# STM32MP25XXAK_I_Os.net
KiCad netlist of a schematic drawn in Altium Designer
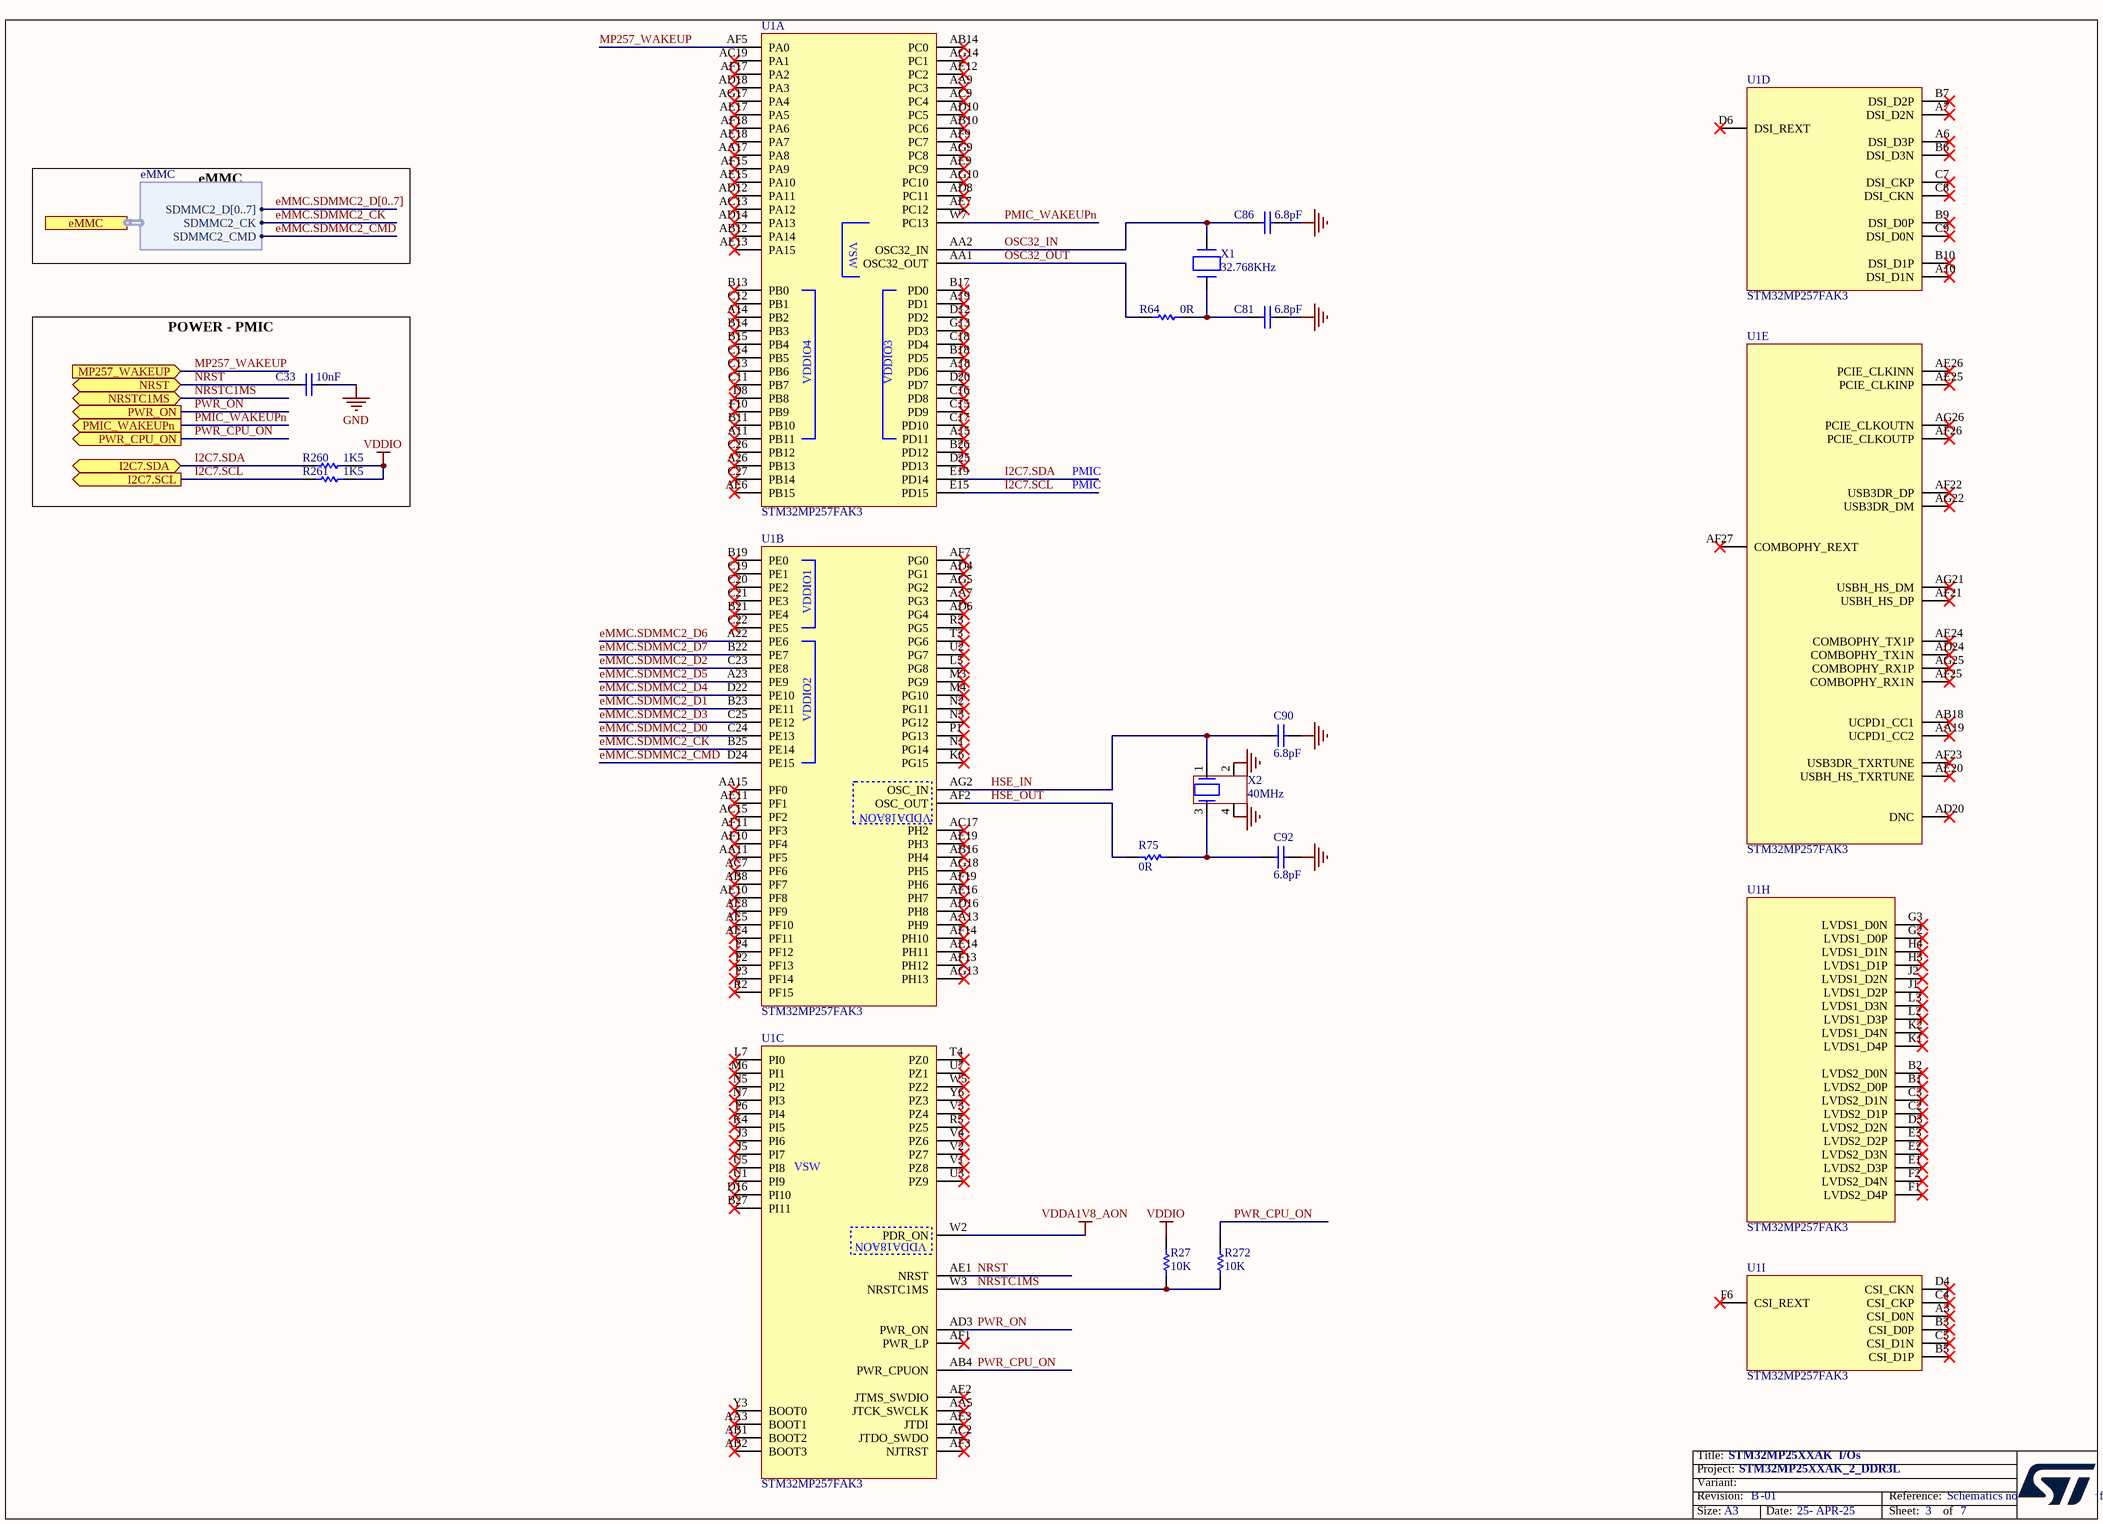
[diagram p0: STM32MP25XXAK I_Os.SchDoc]

(export (version "E")
  (design (tool "Eeschema 10.0.6"))
  (components
    (comp (ref "C33")
      (value "10nF")
      (footprint "C0402")
      (description "Capacitor, MLCC, 10nF, 16V, X7R, 10%, 0402, T=0.5mm")
      (fields
        (field (name "INTERNAL_PART_NUMBER") "MCD-00011")
        (field (name "MANUFACTURER_PART_NUMBER") "CC0402KRX7R7BB103")
        (field (name "PROVIDED_BY") "SUBCO")
      )
      (libsource (lib "MCD_PARTS_database") (part "Capacitor"))
    )
    (comp (ref "C81")
      (value "6.8pF")
      (footprint "C0402")
      (description "Capacitor, MLCC, 6.8pF, 50V, NPO, +-0.25pF, 0402, T=0.5mm")
      (fields
        (field (name "INTERNAL_PART_NUMBER") "MCD-00674")
        (field (name "MANUFACTURER_PART_NUMBER") "CC0402CRNPO9BN6R8")
        (field (name "PROVIDED_BY") "SUBCO")
      )
      (libsource (lib "MCD_PARTS_database") (part "Capacitor"))
    )
    (comp (ref "C86")
      (value "6.8pF")
      (footprint "C0402")
      (description "Capacitor, MLCC, 6.8pF, 50V, NPO, +-0.25pF, 0402, T=0.5mm")
      (fields
        (field (name "INTERNAL_PART_NUMBER") "MCD-00674")
        (field (name "MANUFACTURER_PART_NUMBER") "CC0402CRNPO9BN6R8")
        (field (name "PROVIDED_BY") "SUBCO")
      )
      (libsource (lib "MCD_PARTS_database") (part "Capacitor"))
    )
    (comp (ref "C90")
      (value "6.8pF")
      (footprint "C0402")
      (description "Capacitor, MLCC, 6.8pF, 50V, NPO, +-0.25pF, 0402, T=0.5mm")
      (fields
        (field (name "INTERNAL_PART_NUMBER") "MCD-00674")
        (field (name "MANUFACTURER_PART_NUMBER") "CC0402CRNPO9BN6R8")
        (field (name "PROVIDED_BY") "SUBCO")
      )
      (libsource (lib "MCD_PARTS_database") (part "Capacitor"))
    )
    (comp (ref "C92")
      (value "6.8pF")
      (footprint "C0402")
      (description "Capacitor, MLCC, 6.8pF, 50V, NPO, +-0.25pF, 0402, T=0.5mm")
      (fields
        (field (name "INTERNAL_PART_NUMBER") "MCD-00674")
        (field (name "MANUFACTURER_PART_NUMBER") "CC0402CRNPO9BN6R8")
        (field (name "PROVIDED_BY") "SUBCO")
      )
      (libsource (lib "MCD_PARTS_database") (part "Capacitor"))
    )
    (comp (ref "R27")
      (value "10K")
      (footprint "R0402")
      (description "Resistor,10K,0402,1%,1/16W")
      (fields (field (name "INTERNAL_PART_NUMBER") "MCD-00053") (field (name "BMS_PART_NUMBER") "9131590"))
      (libsource (lib "MCD_PARTS_database") (part "Resistor"))
    )
    (comp (ref "R64")
      (value "0R")
      (footprint "R0402")
      (description "Resistor,0R,0402,5%,1/16W")
      (fields
        (field (name "INTERNAL_PART_NUMBER") "MCD-00052")
        (field (name "MANUFACTURER_PART_NUMBER") "RC0402JR-070RL")
        (field (name "PROVIDED_BY") "SUBCO")
      )
      (libsource (lib "MCD_PARTS_database") (part "Resistor"))
    )
    (comp (ref "R75")
      (value "0R")
      (footprint "R0402")
      (description "Resistor,0R,0402,5%,1/16W")
      (fields
        (field (name "INTERNAL_PART_NUMBER") "MCD-00052")
        (field (name "MANUFACTURER_PART_NUMBER") "RC0402JR-070RL")
        (field (name "PROVIDED_BY") "SUBCO")
      )
      (libsource (lib "MCD_PARTS_database") (part "Resistor"))
    )
    (comp (ref "R260")
      (value "1K5")
      (footprint "R0402")
      (description "Resistor,1K5,0402,1%,1/16W")
      (fields (field (name "INTERNAL_PART_NUMBER") "MCD-00068") (field (name "MANUFACTURER") "YAGEO"))
      (libsource (lib "MCD_PARTS_database") (part "Resistor"))
    )
    (comp (ref "R261")
      (value "1K5")
      (footprint "R0402")
      (description "Resistor,1K5,0402,1%,1/16W")
      (fields (field (name "INTERNAL_PART_NUMBER") "MCD-00068") (field (name "MANUFACTURER") "YAGEO"))
      (libsource (lib "MCD_PARTS_database") (part "Resistor"))
    )
    (comp (ref "R272")
      (value "10K")
      (footprint "R0402")
      (description "Resistor,10K,0402,1%,1/16W")
      (fields (field (name "INTERNAL_PART_NUMBER") "MCD-00053") (field (name "BMS_PART_NUMBER") "9131590"))
      (libsource (lib "MCD_PARTS_database") (part "Resistor"))
    )
    (comp (ref "U1")
      (value "STM32MP257FAK3")
      (footprint "ICC_TFBGA424_14X14_P050_H1P20_CODE-B0A2")
      (description "MPU , 2xCortex-A35@1.5GHz, Cortex-M33@400MHz, TFBGA 14x14, pitch 0.5, 648KB SRAM, With Crypto")
      (fields
        (field (name "INTERNAL_PART_NUMBER") "MCD-03375")
        (field (name "MANUFACTURER") "STMICROELECTRONICS")
      )
      (libsource (lib "MCD_PARTS_database") (part "STM32MP257FAK3"))
    )
    (comp (ref "X1")
      (value "32.768KHz")
      (footprint "CRY_NX2012SA_2P")
      (description "Crystal, 32.768kHz, 6pF, +/-20ppm, 80K, 2.05x1.2mm")
      (fields (field (name "INTERNAL_PART_NUMBER") "MCD-01479") (field (name "BMS_PART_NUMBER") "9157049"))
      (libsource (lib "MCD_PARTS_database") (part "XTAL_2_PINS"))
    )
    (comp (ref "X2")
      (value "40MHz")
      (footprint "CRY_NX1612SA_4P")
      (description "Crystal, 40MHz, 6pF, +/-20ppm, 80R, 1.6x1.2mm")
      (fields (field (name "INTERNAL_PART_NUMBER") "MCD-02344") (field (name "MANUFACTURER") "NDK"))
      (libsource (lib "MCD_PARTS_database") (part "XTAL_4_PINS"))
    )
  )
  (nets
    (net (code "2") (name "/HSE_IN") (class "Default")
      (node (ref "C90") (pin "2") (pinfunction "2_2") (pintype "passive"))
      (node (ref "U1") (pin "AG2") (pinfunction "OSC_IN_AG2") (pintype "passive"))
      (node (ref "X2") (pin "1") (pinfunction "1_1") (pintype "passive"))
    )
    (net (code "3") (name "/HSE_OUT") (class "Default")
      (node (ref "R75") (pin "2") (pinfunction "2_2") (pintype "passive"))
      (node (ref "U1") (pin "AF2") (pinfunction "OSC_OUT_AF2") (pintype "passive"))
    )
    (net (code "4") (name "/I2C7.SCL") (class "Default")
      (node (ref "R261") (pin "1") (pinfunction "1_1") (pintype "passive"))
      (node (ref "U1") (pin "E15") (pinfunction "PD15_E15") (pintype "passive"))
    )
    (net (code "5") (name "/I2C7.SDA") (class "Default")
      (node (ref "R260") (pin "1") (pinfunction "1_1") (pintype "passive"))
      (node (ref "U1") (pin "E19") (pinfunction "PD14_E19") (pintype "passive"))
    )
    (net (code "6") (name "/MP257_WAKEUP") (class "Default")
      (node (ref "U1") (pin "AF5") (pinfunction "PA0_AF5") (pintype "passive"))
    )
    (net (code "7") (name "/NRST") (class "Default")
      (node (ref "C33") (pin "2") (pinfunction "2_2") (pintype "passive"))
      (node (ref "U1") (pin "AE1") (pinfunction "NRST_AE1") (pintype "passive"))
    )
    (net (code "8") (name "/NRSTC1MS") (class "Default")
      (node (ref "R27") (pin "1") (pinfunction "1_1") (pintype "passive"))
      (node (ref "R272") (pin "1") (pinfunction "1_1") (pintype "passive"))
      (node (ref "U1") (pin "W3") (pinfunction "NRSTC1MS_W3") (pintype "passive"))
    )
    (net (code "9") (name "/OSC32_IN") (class "Default")
      (node (ref "C86") (pin "1") (pinfunction "1_1") (pintype "passive"))
      (node (ref "U1") (pin "AA2") (pinfunction "OSC32_IN_AA2") (pintype "passive"))
      (node (ref "X1") (pin "2") (pinfunction "X2_2") (pintype "passive"))
    )
    (net (code "10") (name "/OSC32_OUT") (class "Default")
      (node (ref "R64") (pin "1") (pinfunction "1_1") (pintype "passive"))
      (node (ref "U1") (pin "AA1") (pinfunction "OSC32_OUT_AA1") (pintype "passive"))
    )
    (net (code "11") (name "/PMIC_WAKEUPn") (class "Default")
      (node (ref "U1") (pin "W7") (pinfunction "PC13_W7") (pintype "passive"))
    )
    (net (code "12") (name "/PWR_CPU_ON") (class "Default")
      (node (ref "R272") (pin "2") (pinfunction "2_2") (pintype "passive"))
      (node (ref "U1") (pin "AB4") (pinfunction "PWR_CPUON_AB4") (pintype "passive"))
    )
    (net (code "13") (name "/PWR_ON") (class "Default")
      (node (ref "U1") (pin "AD3") (pinfunction "PWR_ON_AD3") (pintype "passive"))
    )
    (net (code "14") (name "/eMMC.SDMMC2_CK") (class "Default")
      (node (ref "U1") (pin "B25") (pinfunction "PE14_B25") (pintype "passive"))
    )
    (net (code "15") (name "/eMMC.SDMMC2_CMD") (class "Default")
      (node (ref "U1") (pin "D24") (pinfunction "PE15_D24") (pintype "passive"))
    )
    (net (code "16") (name "/eMMC.SDMMC2_D0") (class "Default")
      (node (ref "U1") (pin "C24") (pinfunction "PE13_C24") (pintype "passive"))
    )
    (net (code "17") (name "/eMMC.SDMMC2_D1") (class "Default")
      (node (ref "U1") (pin "B23") (pinfunction "PE11_B23") (pintype "passive"))
    )
    (net (code "18") (name "/eMMC.SDMMC2_D2") (class "Default")
      (node (ref "U1") (pin "C23") (pinfunction "PE8_C23") (pintype "passive"))
    )
    (net (code "19") (name "/eMMC.SDMMC2_D3") (class "Default")
      (node (ref "U1") (pin "C25") (pinfunction "PE12_C25") (pintype "passive"))
    )
    (net (code "20") (name "/eMMC.SDMMC2_D4") (class "Default")
      (node (ref "U1") (pin "D22") (pinfunction "PE10_D22") (pintype "passive"))
    )
    (net (code "21") (name "/eMMC.SDMMC2_D5") (class "Default")
      (node (ref "U1") (pin "A23") (pinfunction "PE9_A23") (pintype "passive"))
    )
    (net (code "22") (name "/eMMC.SDMMC2_D6") (class "Default")
      (node (ref "U1") (pin "A22") (pinfunction "PE6_A22") (pintype "passive"))
    )
    (net (code "23") (name "/eMMC.SDMMC2_D7") (class "Default")
      (node (ref "U1") (pin "B22") (pinfunction "PE7_B22") (pintype "passive"))
    )
    (net (code "26") (name "GND") (class "Default")
      (node (ref "C33") (pin "1") (pinfunction "1_1") (pintype "passive"))
      (node (ref "C81") (pin "2") (pinfunction "2_2") (pintype "passive"))
      (node (ref "C86") (pin "2") (pinfunction "2_2") (pintype "passive"))
      (node (ref "C90") (pin "1") (pinfunction "1_1") (pintype "passive"))
      (node (ref "C92") (pin "2") (pinfunction "2_2") (pintype "passive"))
      (node (ref "X2") (pin "2") (pinfunction "2_2") (pintype "passive"))
      (node (ref "X2") (pin "4") (pinfunction "4_4") (pintype "passive"))
    )
    (net (code "27") (name "Net-(C92-Pad1)") (class "Default")
      (node (ref "C92") (pin "1") (pinfunction "1_1") (pintype "passive"))
      (node (ref "R75") (pin "1") (pinfunction "1_1") (pintype "passive"))
      (node (ref "X2") (pin "3") (pinfunction "3_3") (pintype "passive"))
    )
    (net (code "28") (name "Net-(X1-X1)") (class "Default")
      (node (ref "C81") (pin "1") (pinfunction "1_1") (pintype "passive"))
      (node (ref "R64") (pin "2") (pinfunction "2_2") (pintype "passive"))
      (node (ref "X1") (pin "1") (pinfunction "X1_1") (pintype "passive"))
    )
    (net (code "29") (name "VDDA1V8_AON") (class "Default")
      (node (ref "U1") (pin "W2") (pinfunction "PDR_ON_W2") (pintype "passive"))
    )
    (net (code "30") (name "VDDIO") (class "Default")
      (node (ref "R260") (pin "2") (pinfunction "2_2") (pintype "passive"))
      (node (ref "R261") (pin "2") (pinfunction "2_2") (pintype "passive"))
      (node (ref "R27") (pin "2") (pinfunction "2_2") (pintype "passive"))
    )
    (net (code "31") (name "unconnected-(U1A-PA1-PadAC19)") (class "Default")
      (node (ref "U1") (pin "AC19") (pinfunction "PA1_AC19") (pintype "passive+no_connect"))
    )
    (net (code "32") (name "unconnected-(U1A-PA2-PadAF17)") (class "Default")
      (node (ref "U1") (pin "AF17") (pinfunction "PA2_AF17") (pintype "passive+no_connect"))
    )
    (net (code "33") (name "unconnected-(U1A-PA3-PadAD18)") (class "Default")
      (node (ref "U1") (pin "AD18") (pinfunction "PA3_AD18") (pintype "passive+no_connect"))
    )
    (net (code "34") (name "unconnected-(U1A-PA4-PadAG17)") (class "Default")
      (node (ref "U1") (pin "AG17") (pinfunction "PA4_AG17") (pintype "passive+no_connect"))
    )
    (net (code "35") (name "unconnected-(U1A-PA5-PadAE17)") (class "Default")
      (node (ref "U1") (pin "AE17") (pinfunction "PA5_AE17") (pintype "passive+no_connect"))
    )
    (net (code "36") (name "unconnected-(U1A-PA6-PadAF18)") (class "Default")
      (node (ref "U1") (pin "AF18") (pinfunction "PA6_AF18") (pintype "passive+no_connect"))
    )
    (net (code "37") (name "unconnected-(U1A-PA7-PadAE18)") (class "Default")
      (node (ref "U1") (pin "AE18") (pinfunction "PA7_AE18") (pintype "passive+no_connect"))
    )
    (net (code "38") (name "unconnected-(U1A-PA8-PadAA17)") (class "Default")
      (node (ref "U1") (pin "AA17") (pinfunction "PA8_AA17") (pintype "passive+no_connect"))
    )
    (net (code "39") (name "unconnected-(U1A-PA9-PadAF15)") (class "Default")
      (node (ref "U1") (pin "AF15") (pinfunction "PA9_AF15") (pintype "passive+no_connect"))
    )
    (net (code "40") (name "unconnected-(U1A-PA10-PadAE15)") (class "Default")
      (node (ref "U1") (pin "AE15") (pinfunction "PA10_AE15") (pintype "passive+no_connect"))
    )
    (net (code "41") (name "unconnected-(U1A-PA11-PadAD12)") (class "Default")
      (node (ref "U1") (pin "AD12") (pinfunction "PA11_AD12") (pintype "passive+no_connect"))
    )
    (net (code "42") (name "unconnected-(U1A-PA12-PadAC13)") (class "Default")
      (node (ref "U1") (pin "AC13") (pinfunction "PA12_AC13") (pintype "passive+no_connect"))
    )
    (net (code "43") (name "unconnected-(U1A-PA13-PadAD14)") (class "Default")
      (node (ref "U1") (pin "AD14") (pinfunction "PA13_AD14") (pintype "passive+no_connect"))
    )
    (net (code "44") (name "unconnected-(U1A-PA14-PadAB12)") (class "Default")
      (node (ref "U1") (pin "AB12") (pinfunction "PA14_AB12") (pintype "passive+no_connect"))
    )
    (net (code "45") (name "unconnected-(U1A-PA15-PadAE13)") (class "Default")
      (node (ref "U1") (pin "AE13") (pinfunction "PA15_AE13") (pintype "passive+no_connect"))
    )
    (net (code "46") (name "unconnected-(U1A-PB0-PadB13)") (class "Default")
      (node (ref "U1") (pin "B13") (pinfunction "PB0_B13") (pintype "passive+no_connect"))
    )
    (net (code "47") (name "unconnected-(U1A-PB1-PadC12)") (class "Default")
      (node (ref "U1") (pin "C12") (pinfunction "PB1_C12") (pintype "passive+no_connect"))
    )
    (net (code "48") (name "unconnected-(U1A-PB2-PadA14)") (class "Default")
      (node (ref "U1") (pin "A14") (pinfunction "PB2_A14") (pintype "passive+no_connect"))
    )
    (net (code "49") (name "unconnected-(U1A-PB3-PadB14)") (class "Default")
      (node (ref "U1") (pin "B14") (pinfunction "PB3_B14") (pintype "passive+no_connect"))
    )
    (net (code "50") (name "unconnected-(U1A-PB4-PadB15)") (class "Default")
      (node (ref "U1") (pin "B15") (pinfunction "PB4_B15") (pintype "passive+no_connect"))
    )
    (net (code "51") (name "unconnected-(U1A-PB5-PadC14)") (class "Default")
      (node (ref "U1") (pin "C14") (pinfunction "PB5_C14") (pintype "passive+no_connect"))
    )
    (net (code "52") (name "unconnected-(U1A-PB6-PadC13)") (class "Default")
      (node (ref "U1") (pin "C13") (pinfunction "PB6_C13") (pintype "passive+no_connect"))
    )
    (net (code "53") (name "unconnected-(U1A-PB7-PadC11)") (class "Default")
      (node (ref "U1") (pin "C11") (pinfunction "PB7_C11") (pintype "passive+no_connect"))
    )
    (net (code "54") (name "unconnected-(U1A-PB8-PadD8)") (class "Default")
      (node (ref "U1") (pin "D8") (pinfunction "PB8_D8") (pintype "passive+no_connect"))
    )
    (net (code "55") (name "unconnected-(U1A-PB9-PadF10)") (class "Default")
      (node (ref "U1") (pin "F10") (pinfunction "PB9_F10") (pintype "passive+no_connect"))
    )
    (net (code "56") (name "unconnected-(U1A-PB10-PadB11)") (class "Default")
      (node (ref "U1") (pin "B11") (pinfunction "PB10_B11") (pintype "passive+no_connect"))
    )
    (net (code "57") (name "unconnected-(U1A-PB11-PadA11)") (class "Default")
      (node (ref "U1") (pin "A11") (pinfunction "PB11_A11") (pintype "passive+no_connect"))
    )
    (net (code "58") (name "unconnected-(U1A-PB12-PadC26)") (class "Default")
      (node (ref "U1") (pin "C26") (pinfunction "PB12_C26") (pintype "passive+no_connect"))
    )
    (net (code "59") (name "unconnected-(U1A-PB13-PadA26)") (class "Default")
      (node (ref "U1") (pin "A26") (pinfunction "PB13_A26") (pintype "passive+no_connect"))
    )
    (net (code "60") (name "unconnected-(U1A-PB14-PadC27)") (class "Default")
      (node (ref "U1") (pin "C27") (pinfunction "PB14_C27") (pintype "passive+no_connect"))
    )
    (net (code "61") (name "unconnected-(U1A-PB15-PadAE6)") (class "Default")
      (node (ref "U1") (pin "AE6") (pinfunction "PB15_AE6") (pintype "passive+no_connect"))
    )
    (net (code "62") (name "unconnected-(U1A-PC0-PadAB14)") (class "Default")
      (node (ref "U1") (pin "AB14") (pinfunction "PC0_AB14") (pintype "passive+no_connect"))
    )
    (net (code "63") (name "unconnected-(U1A-PC1-PadAG14)") (class "Default")
      (node (ref "U1") (pin "AG14") (pinfunction "PC1_AG14") (pintype "passive+no_connect"))
    )
    (net (code "64") (name "unconnected-(U1A-PC2-PadAE12)") (class "Default")
      (node (ref "U1") (pin "AE12") (pinfunction "PC2_AE12") (pintype "passive+no_connect"))
    )
    (net (code "65") (name "unconnected-(U1A-PC3-PadAA9)") (class "Default")
      (node (ref "U1") (pin "AA9") (pinfunction "PC3_AA9") (pintype "passive+no_connect"))
    )
    (net (code "66") (name "unconnected-(U1A-PC4-PadAC9)") (class "Default")
      (node (ref "U1") (pin "AC9") (pinfunction "PC4_AC9") (pintype "passive+no_connect"))
    )
    (net (code "67") (name "unconnected-(U1A-PC5-PadAD10)") (class "Default")
      (node (ref "U1") (pin "AD10") (pinfunction "PC5_AD10") (pintype "passive+no_connect"))
    )
    (net (code "68") (name "unconnected-(U1A-PC6-PadAB10)") (class "Default")
      (node (ref "U1") (pin "AB10") (pinfunction "PC6_AB10") (pintype "passive+no_connect"))
    )
    (net (code "69") (name "unconnected-(U1A-PC7-PadAF9)") (class "Default")
      (node (ref "U1") (pin "AF9") (pinfunction "PC7_AF9") (pintype "passive+no_connect"))
    )
    (net (code "70") (name "unconnected-(U1A-PC8-PadAG9)") (class "Default")
      (node (ref "U1") (pin "AG9") (pinfunction "PC8_AG9") (pintype "passive+no_connect"))
    )
    (net (code "71") (name "unconnected-(U1A-PC9-PadAE9)") (class "Default")
      (node (ref "U1") (pin "AE9") (pinfunction "PC9_AE9") (pintype "passive+no_connect"))
    )
    (net (code "72") (name "unconnected-(U1A-PC10-PadAG10)") (class "Default")
      (node (ref "U1") (pin "AG10") (pinfunction "PC10_AG10") (pintype "passive+no_connect"))
    )
    (net (code "73") (name "unconnected-(U1A-PC11-PadAD8)") (class "Default")
      (node (ref "U1") (pin "AD8") (pinfunction "PC11_AD8") (pintype "passive+no_connect"))
    )
    (net (code "74") (name "unconnected-(U1A-PC12-PadAE7)") (class "Default")
      (node (ref "U1") (pin "AE7") (pinfunction "PC12_AE7") (pintype "passive+no_connect"))
    )
    (net (code "75") (name "unconnected-(U1A-PD0-PadB17)") (class "Default")
      (node (ref "U1") (pin "B17") (pinfunction "PD0_B17") (pintype "passive+no_connect"))
    )
    (net (code "76") (name "unconnected-(U1A-PD1-PadA19)") (class "Default")
      (node (ref "U1") (pin "A19") (pinfunction "PD1_A19") (pintype "passive+no_connect"))
    )
    (net (code "77") (name "unconnected-(U1A-PD2-PadD12)") (class "Default")
      (node (ref "U1") (pin "D12") (pinfunction "PD2_D12") (pintype "passive+no_connect"))
    )
    (net (code "78") (name "unconnected-(U1A-PD3-PadG13)") (class "Default")
      (node (ref "U1") (pin "G13") (pinfunction "PD3_G13") (pintype "passive+no_connect"))
    )
    (net (code "79") (name "unconnected-(U1A-PD4-PadC18)") (class "Default")
      (node (ref "U1") (pin "C18") (pinfunction "PD4_C18") (pintype "passive+no_connect"))
    )
    (net (code "80") (name "unconnected-(U1A-PD5-PadB18)") (class "Default")
      (node (ref "U1") (pin "B18") (pinfunction "PD5_B18") (pintype "passive+no_connect"))
    )
    (net (code "81") (name "unconnected-(U1A-PD6-PadA18)") (class "Default")
      (node (ref "U1") (pin "A18") (pinfunction "PD6_A18") (pintype "passive+no_connect"))
    )
    (net (code "82") (name "unconnected-(U1A-PD7-PadD20)") (class "Default")
      (node (ref "U1") (pin "D20") (pinfunction "PD7_D20") (pintype "passive+no_connect"))
    )
    (net (code "83") (name "unconnected-(U1A-PD8-PadC16)") (class "Default")
      (node (ref "U1") (pin "C16") (pinfunction "PD8_C16") (pintype "passive+no_connect"))
    )
    (net (code "84") (name "unconnected-(U1A-PD9-PadC15)") (class "Default")
      (node (ref "U1") (pin "C15") (pinfunction "PD9_C15") (pintype "passive+no_connect"))
    )
    (net (code "85") (name "unconnected-(U1A-PD10-PadC17)") (class "Default")
      (node (ref "U1") (pin "C17") (pinfunction "PD10_C17") (pintype "passive+no_connect"))
    )
    (net (code "86") (name "unconnected-(U1A-PD11-PadA15)") (class "Default")
      (node (ref "U1") (pin "A15") (pinfunction "PD11_A15") (pintype "passive+no_connect"))
    )
    (net (code "87") (name "unconnected-(U1A-PD12-PadB26)") (class "Default")
      (node (ref "U1") (pin "B26") (pinfunction "PD12_B26") (pintype "passive+no_connect"))
    )
    (net (code "88") (name "unconnected-(U1A-PD13-PadD25)") (class "Default")
      (node (ref "U1") (pin "D25") (pinfunction "PD13_D25") (pintype "passive+no_connect"))
    )
    (net (code "89") (name "unconnected-(U1B-PE0-PadB19)") (class "Default")
      (node (ref "U1") (pin "B19") (pinfunction "PE0_B19") (pintype "passive+no_connect"))
    )
    (net (code "90") (name "unconnected-(U1B-PE1-PadC19)") (class "Default")
      (node (ref "U1") (pin "C19") (pinfunction "PE1_C19") (pintype "passive+no_connect"))
    )
    (net (code "91") (name "unconnected-(U1B-PE2-PadC20)") (class "Default")
      (node (ref "U1") (pin "C20") (pinfunction "PE2_C20") (pintype "passive+no_connect"))
    )
    (net (code "92") (name "unconnected-(U1B-PE3-PadC21)") (class "Default")
      (node (ref "U1") (pin "C21") (pinfunction "PE3_C21") (pintype "passive+no_connect"))
    )
    (net (code "93") (name "unconnected-(U1B-PE4-PadB21)") (class "Default")
      (node (ref "U1") (pin "B21") (pinfunction "PE4_B21") (pintype "passive+no_connect"))
    )
    (net (code "94") (name "unconnected-(U1B-PE5-PadC22)") (class "Default")
      (node (ref "U1") (pin "C22") (pinfunction "PE5_C22") (pintype "passive+no_connect"))
    )
    (net (code "95") (name "unconnected-(U1B-PF0-PadAA15)") (class "Default")
      (node (ref "U1") (pin "AA15") (pinfunction "PF0_AA15") (pintype "passive+no_connect"))
    )
    (net (code "96") (name "unconnected-(U1B-PF1-PadAE11)") (class "Default")
      (node (ref "U1") (pin "AE11") (pinfunction "PF1_AE11") (pintype "passive+no_connect"))
    )
    (net (code "97") (name "unconnected-(U1B-PF2-PadAC15)") (class "Default")
      (node (ref "U1") (pin "AC15") (pinfunction "PF2_AC15") (pintype "passive+no_connect"))
    )
    (net (code "98") (name "unconnected-(U1B-PF3-PadAF11)") (class "Default")
      (node (ref "U1") (pin "AF11") (pinfunction "PF3_AF11") (pintype "passive+no_connect"))
    )
    (net (code "99") (name "unconnected-(U1B-PF4-PadAF10)") (class "Default")
      (node (ref "U1") (pin "AF10") (pinfunction "PF4_AF10") (pintype "passive+no_connect"))
    )
    (net (code "100") (name "unconnected-(U1B-PF5-PadAA11)") (class "Default")
      (node (ref "U1") (pin "AA11") (pinfunction "PF5_AA11") (pintype "passive+no_connect"))
    )
    (net (code "101") (name "unconnected-(U1B-PF6-PadAC7)") (class "Default")
      (node (ref "U1") (pin "AC7") (pinfunction "PF6_AC7") (pintype "passive+no_connect"))
    )
    (net (code "102") (name "unconnected-(U1B-PF7-PadAB8)") (class "Default")
      (node (ref "U1") (pin "AB8") (pinfunction "PF7_AB8") (pintype "passive+no_connect"))
    )
    (net (code "103") (name "unconnected-(U1B-PF8-PadAE10)") (class "Default")
      (node (ref "U1") (pin "AE10") (pinfunction "PF8_AE10") (pintype "passive+no_connect"))
    )
    (net (code "104") (name "unconnected-(U1B-PF9-PadAE8)") (class "Default")
      (node (ref "U1") (pin "AE8") (pinfunction "PF9_AE8") (pintype "passive+no_connect"))
    )
    (net (code "105") (name "unconnected-(U1B-PF10-PadAE5)") (class "Default")
      (node (ref "U1") (pin "AE5") (pinfunction "PF10_AE5") (pintype "passive+no_connect"))
    )
    (net (code "106") (name "unconnected-(U1B-PF11-PadAE4)") (class "Default")
      (node (ref "U1") (pin "AE4") (pinfunction "PF11_AE4") (pintype "passive+no_connect"))
    )
    (net (code "107") (name "unconnected-(U1B-PF12-PadP4)") (class "Default")
      (node (ref "U1") (pin "P4") (pinfunction "PF12_P4") (pintype "passive+no_connect"))
    )
    (net (code "108") (name "unconnected-(U1B-PF13-PadP2)") (class "Default")
      (node (ref "U1") (pin "P2") (pinfunction "PF13_P2") (pintype "passive+no_connect"))
    )
    (net (code "109") (name "unconnected-(U1B-PF14-PadP3)") (class "Default")
      (node (ref "U1") (pin "P3") (pinfunction "PF14_P3") (pintype "passive+no_connect"))
    )
    (net (code "110") (name "unconnected-(U1B-PF15-PadR2)") (class "Default")
      (node (ref "U1") (pin "R2") (pinfunction "PF15_R2") (pintype "passive+no_connect"))
    )
    (net (code "111") (name "unconnected-(U1B-PG0-PadAF7)") (class "Default")
      (node (ref "U1") (pin "AF7") (pinfunction "PG0_AF7") (pintype "passive+no_connect"))
    )
    (net (code "112") (name "unconnected-(U1B-PG1-PadAD4)") (class "Default")
      (node (ref "U1") (pin "AD4") (pinfunction "PG1_AD4") (pintype "passive+no_connect"))
    )
    (net (code "113") (name "unconnected-(U1B-PG2-PadAG5)") (class "Default")
      (node (ref "U1") (pin "AG5") (pinfunction "PG2_AG5") (pintype "passive+no_connect"))
    )
    (net (code "114") (name "unconnected-(U1B-PG3-PadAA7)") (class "Default")
      (node (ref "U1") (pin "AA7") (pinfunction "PG3_AA7") (pintype "passive+no_connect"))
    )
    (net (code "115") (name "unconnected-(U1B-PG4-PadAD6)") (class "Default")
      (node (ref "U1") (pin "AD6") (pinfunction "PG4_AD6") (pintype "passive+no_connect"))
    )
    (net (code "116") (name "unconnected-(U1B-PG5-PadR3)") (class "Default")
      (node (ref "U1") (pin "R3") (pinfunction "PG5_R3") (pintype "passive+no_connect"))
    )
    (net (code "117") (name "unconnected-(U1B-PG6-PadT3)") (class "Default")
      (node (ref "U1") (pin "T3") (pinfunction "PG6_T3") (pintype "passive+no_connect"))
    )
    (net (code "118") (name "unconnected-(U1B-PG7-PadU2)") (class "Default")
      (node (ref "U1") (pin "U2") (pinfunction "PG7_U2") (pintype "passive+no_connect"))
    )
    (net (code "119") (name "unconnected-(U1B-PG8-PadL5)") (class "Default")
      (node (ref "U1") (pin "L5") (pinfunction "PG8_L5") (pintype "passive+no_connect"))
    )
    (net (code "120") (name "unconnected-(U1B-PG9-PadM3)") (class "Default")
      (node (ref "U1") (pin "M3") (pinfunction "PG9_M3") (pintype "passive+no_connect"))
    )
    (net (code "121") (name "unconnected-(U1B-PG10-PadM4)") (class "Default")
      (node (ref "U1") (pin "M4") (pinfunction "PG10_M4") (pintype "passive+no_connect"))
    )
    (net (code "122") (name "unconnected-(U1B-PG11-PadN2)") (class "Default")
      (node (ref "U1") (pin "N2") (pinfunction "PG11_N2") (pintype "passive+no_connect"))
    )
    (net (code "123") (name "unconnected-(U1B-PG12-PadN3)") (class "Default")
      (node (ref "U1") (pin "N3") (pinfunction "PG12_N3") (pintype "passive+no_connect"))
    )
    (net (code "124") (name "unconnected-(U1B-PG13-PadP1)") (class "Default")
      (node (ref "U1") (pin "P1") (pinfunction "PG13_P1") (pintype "passive+no_connect"))
    )
    (net (code "125") (name "unconnected-(U1B-PG14-PadN1)") (class "Default")
      (node (ref "U1") (pin "N1") (pinfunction "PG14_N1") (pintype "passive+no_connect"))
    )
    (net (code "126") (name "unconnected-(U1B-PG15-PadK6)") (class "Default")
      (node (ref "U1") (pin "K6") (pinfunction "PG15_K6") (pintype "passive+no_connect"))
    )
    (net (code "127") (name "unconnected-(U1B-PH2-PadAC17)") (class "Default")
      (node (ref "U1") (pin "AC17") (pinfunction "PH2_AC17") (pintype "passive+no_connect"))
    )
    (net (code "128") (name "unconnected-(U1B-PH3-PadAE19)") (class "Default")
      (node (ref "U1") (pin "AE19") (pinfunction "PH3_AE19") (pintype "passive+no_connect"))
    )
    (net (code "129") (name "unconnected-(U1B-PH4-PadAB16)") (class "Default")
      (node (ref "U1") (pin "AB16") (pinfunction "PH4_AB16") (pintype "passive+no_connect"))
    )
    (net (code "130") (name "unconnected-(U1B-PH5-PadAG18)") (class "Default")
      (node (ref "U1") (pin "AG18") (pinfunction "PH5_AG18") (pintype "passive+no_connect"))
    )
    (net (code "131") (name "unconnected-(U1B-PH6-PadAF19)") (class "Default")
      (node (ref "U1") (pin "AF19") (pinfunction "PH6_AF19") (pintype "passive+no_connect"))
    )
    (net (code "132") (name "unconnected-(U1B-PH7-PadAE16)") (class "Default")
      (node (ref "U1") (pin "AE16") (pinfunction "PH7_AE16") (pintype "passive+no_connect"))
    )
    (net (code "133") (name "unconnected-(U1B-PH8-PadAD16)") (class "Default")
      (node (ref "U1") (pin "AD16") (pinfunction "PH8_AD16") (pintype "passive+no_connect"))
    )
    (net (code "134") (name "unconnected-(U1B-PH9-PadAA13)") (class "Default")
      (node (ref "U1") (pin "AA13") (pinfunction "PH9_AA13") (pintype "passive+no_connect"))
    )
    (net (code "135") (name "unconnected-(U1B-PH10-PadAF14)") (class "Default")
      (node (ref "U1") (pin "AF14") (pinfunction "PH10_AF14") (pintype "passive+no_connect"))
    )
    (net (code "136") (name "unconnected-(U1B-PH11-PadAE14)") (class "Default")
      (node (ref "U1") (pin "AE14") (pinfunction "PH11_AE14") (pintype "passive+no_connect"))
    )
    (net (code "137") (name "unconnected-(U1B-PH12-PadAF13)") (class "Default")
      (node (ref "U1") (pin "AF13") (pinfunction "PH12_AF13") (pintype "passive+no_connect"))
    )
    (net (code "138") (name "unconnected-(U1B-PH13-PadAG13)") (class "Default")
      (node (ref "U1") (pin "AG13") (pinfunction "PH13_AG13") (pintype "passive+no_connect"))
    )
    (net (code "139") (name "unconnected-(U1C-BOOT0-PadY3)") (class "Default")
      (node (ref "U1") (pin "Y3") (pinfunction "BOOT0_Y3") (pintype "passive+no_connect"))
    )
    (net (code "140") (name "unconnected-(U1C-BOOT1-PadAA3)") (class "Default")
      (node (ref "U1") (pin "AA3") (pinfunction "BOOT1_AA3") (pintype "passive+no_connect"))
    )
    (net (code "141") (name "unconnected-(U1C-BOOT2-PadAB1)") (class "Default")
      (node (ref "U1") (pin "AB1") (pinfunction "BOOT2_AB1") (pintype "passive+no_connect"))
    )
    (net (code "142") (name "unconnected-(U1C-BOOT3-PadAB2)") (class "Default")
      (node (ref "U1") (pin "AB2") (pinfunction "BOOT3_AB2") (pintype "passive+no_connect"))
    )
    (net (code "143") (name "unconnected-(U1C-JTCK_SWCLK-PadAA5)") (class "Default")
      (node (ref "U1") (pin "AA5") (pinfunction "JTCK_SWCLK_AA5") (pintype "passive+no_connect"))
    )
    (net (code "144") (name "unconnected-(U1C-JTDI-PadAE3)") (class "Default")
      (node (ref "U1") (pin "AE3") (pinfunction "JTDI_AE3") (pintype "passive+no_connect"))
    )
    (net (code "145") (name "unconnected-(U1C-JTDO_SWDO-PadAC2)") (class "Default")
      (node (ref "U1") (pin "AC2") (pinfunction "JTDO_SWDO_AC2") (pintype "passive+no_connect"))
    )
    (net (code "146") (name "unconnected-(U1C-JTMS_SWDIO-PadAE2)") (class "Default")
      (node (ref "U1") (pin "AE2") (pinfunction "JTMS_SWDIO_AE2") (pintype "passive+no_connect"))
    )
    (net (code "147") (name "unconnected-(U1C-NJTRST-PadAF3)") (class "Default")
      (node (ref "U1") (pin "AF3") (pinfunction "NJTRST_AF3") (pintype "passive+no_connect"))
    )
    (net (code "148") (name "unconnected-(U1C-PI0-PadL7)") (class "Default")
      (node (ref "U1") (pin "L7") (pinfunction "PI0_L7") (pintype "passive+no_connect"))
    )
    (net (code "149") (name "unconnected-(U1C-PI1-PadM6)") (class "Default")
      (node (ref "U1") (pin "M6") (pinfunction "PI1_M6") (pintype "passive+no_connect"))
    )
    (net (code "150") (name "unconnected-(U1C-PI2-PadN5)") (class "Default")
      (node (ref "U1") (pin "N5") (pinfunction "PI2_N5") (pintype "passive+no_connect"))
    )
    (net (code "151") (name "unconnected-(U1C-PI3-PadN7)") (class "Default")
      (node (ref "U1") (pin "N7") (pinfunction "PI3_N7") (pintype "passive+no_connect"))
    )
    (net (code "152") (name "unconnected-(U1C-PI4-PadP6)") (class "Default")
      (node (ref "U1") (pin "P6") (pinfunction "PI4_P6") (pintype "passive+no_connect"))
    )
    (net (code "153") (name "unconnected-(U1C-PI5-PadK4)") (class "Default")
      (node (ref "U1") (pin "K4") (pinfunction "PI5_K4") (pintype "passive+no_connect"))
    )
    (net (code "154") (name "unconnected-(U1C-PI6-PadJ3)") (class "Default")
      (node (ref "U1") (pin "J3") (pinfunction "PI6_J3") (pintype "passive+no_connect"))
    )
    (net (code "155") (name "unconnected-(U1C-PI7-PadJ5)") (class "Default")
      (node (ref "U1") (pin "J5") (pinfunction "PI7_J5") (pintype "passive+no_connect"))
    )
    (net (code "156") (name "unconnected-(U1C-PI8-PadU5)") (class "Default")
      (node (ref "U1") (pin "U5") (pinfunction "PI8_U5") (pintype "passive+no_connect"))
    )
    (net (code "157") (name "unconnected-(U1C-PI9-PadU1)") (class "Default")
      (node (ref "U1") (pin "U1") (pinfunction "PI9_U1") (pintype "passive+no_connect"))
    )
    (net (code "158") (name "unconnected-(U1C-PI10-PadD16)") (class "Default")
      (node (ref "U1") (pin "D16") (pinfunction "PI10_D16") (pintype "passive+no_connect"))
    )
    (net (code "159") (name "unconnected-(U1C-PI11-PadB27)") (class "Default")
      (node (ref "U1") (pin "B27") (pinfunction "PI11_B27") (pintype "passive+no_connect"))
    )
    (net (code "160") (name "unconnected-(U1C-PWR_LP-PadAF1)") (class "Default")
      (node (ref "U1") (pin "AF1") (pinfunction "PWR_LP_AF1") (pintype "passive+no_connect"))
    )
    (net (code "161") (name "unconnected-(U1C-PZ0-PadT4)") (class "Default")
      (node (ref "U1") (pin "T4") (pinfunction "PZ0_T4") (pintype "passive+no_connect"))
    )
    (net (code "162") (name "unconnected-(U1C-PZ1-PadU7)") (class "Default")
      (node (ref "U1") (pin "U7") (pinfunction "PZ1_U7") (pintype "passive+no_connect"))
    )
    (net (code "163") (name "unconnected-(U1C-PZ2-PadW5)") (class "Default")
      (node (ref "U1") (pin "W5") (pinfunction "PZ2_W5") (pintype "passive+no_connect"))
    )
    (net (code "164") (name "unconnected-(U1C-PZ3-PadY6)") (class "Default")
      (node (ref "U1") (pin "Y6") (pinfunction "PZ3_Y6") (pintype "passive+no_connect"))
    )
    (net (code "165") (name "unconnected-(U1C-PZ4-PadV3)") (class "Default")
      (node (ref "U1") (pin "V3") (pinfunction "PZ4_V3") (pintype "passive+no_connect"))
    )
    (net (code "166") (name "unconnected-(U1C-PZ5-PadR5)") (class "Default")
      (node (ref "U1") (pin "R5") (pinfunction "PZ5_R5") (pintype "passive+no_connect"))
    )
    (net (code "167") (name "unconnected-(U1C-PZ6-PadV4)") (class "Default")
      (node (ref "U1") (pin "V4") (pinfunction "PZ6_V4") (pintype "passive+no_connect"))
    )
    (net (code "168") (name "unconnected-(U1C-PZ7-PadV2)") (class "Default")
      (node (ref "U1") (pin "V2") (pinfunction "PZ7_V2") (pintype "passive+no_connect"))
    )
    (net (code "169") (name "unconnected-(U1C-PZ8-PadV1)") (class "Default")
      (node (ref "U1") (pin "V1") (pinfunction "PZ8_V1") (pintype "passive+no_connect"))
    )
    (net (code "170") (name "unconnected-(U1C-PZ9-PadU3)") (class "Default")
      (node (ref "U1") (pin "U3") (pinfunction "PZ9_U3") (pintype "passive+no_connect"))
    )
    (net (code "171") (name "unconnected-(U1D-DSI_CKN-PadC8)") (class "Default")
      (node (ref "U1") (pin "C8") (pinfunction "DSI_CKN_C8") (pintype "passive+no_connect"))
    )
    (net (code "172") (name "unconnected-(U1D-DSI_CKP-PadC7)") (class "Default")
      (node (ref "U1") (pin "C7") (pinfunction "DSI_CKP_C7") (pintype "passive+no_connect"))
    )
    (net (code "173") (name "unconnected-(U1D-DSI_D0N-PadC9)") (class "Default")
      (node (ref "U1") (pin "C9") (pinfunction "DSI_D0N_C9") (pintype "passive+no_connect"))
    )
    (net (code "174") (name "unconnected-(U1D-DSI_D0P-PadB9)") (class "Default")
      (node (ref "U1") (pin "B9") (pinfunction "DSI_D0P_B9") (pintype "passive+no_connect"))
    )
    (net (code "175") (name "unconnected-(U1D-DSI_D1N-PadA10)") (class "Default")
      (node (ref "U1") (pin "A10") (pinfunction "DSI_D1N_A10") (pintype "passive+no_connect"))
    )
    (net (code "176") (name "unconnected-(U1D-DSI_D1P-PadB10)") (class "Default")
      (node (ref "U1") (pin "B10") (pinfunction "DSI_D1P_B10") (pintype "passive+no_connect"))
    )
    (net (code "177") (name "unconnected-(U1D-DSI_D2N-PadA7)") (class "Default")
      (node (ref "U1") (pin "A7") (pinfunction "DSI_D2N_A7") (pintype "passive+no_connect"))
    )
    (net (code "178") (name "unconnected-(U1D-DSI_D2P-PadB7)") (class "Default")
      (node (ref "U1") (pin "B7") (pinfunction "DSI_D2P_B7") (pintype "passive+no_connect"))
    )
    (net (code "179") (name "unconnected-(U1D-DSI_D3N-PadB6)") (class "Default")
      (node (ref "U1") (pin "B6") (pinfunction "DSI_D3N_B6") (pintype "passive+no_connect"))
    )
    (net (code "180") (name "unconnected-(U1D-DSI_D3P-PadA6)") (class "Default")
      (node (ref "U1") (pin "A6") (pinfunction "DSI_D3P_A6") (pintype "passive+no_connect"))
    )
    (net (code "181") (name "unconnected-(U1D-DSI_REXT-PadD6)") (class "Default")
      (node (ref "U1") (pin "D6") (pinfunction "DSI_REXT_D6") (pintype "passive+no_connect"))
    )
    (net (code "182") (name "unconnected-(U1E-COMBOPHY_REXT-PadAF27)") (class "Default")
      (node (ref "U1") (pin "AF27") (pinfunction "COMBOPHY_REXT_AF27") (pintype "passive+no_connect"))
    )
    (net (code "183") (name "unconnected-(U1E-COMBOPHY_RX1N-PadAF25)") (class "Default")
      (node (ref "U1") (pin "AF25") (pinfunction "COMBOPHY_RX1N_AF25") (pintype "passive+no_connect"))
    )
    (net (code "184") (name "unconnected-(U1E-COMBOPHY_RX1P-PadAG25)") (class "Default")
      (node (ref "U1") (pin "AG25") (pinfunction "COMBOPHY_RX1P_AG25") (pintype "passive+no_connect"))
    )
    (net (code "185") (name "unconnected-(U1E-COMBOPHY_TX1N-PadAD24)") (class "Default")
      (node (ref "U1") (pin "AD24") (pinfunction "COMBOPHY_TX1N_AD24") (pintype "passive+no_connect"))
    )
    (net (code "186") (name "unconnected-(U1E-COMBOPHY_TX1P-PadAE24)") (class "Default")
      (node (ref "U1") (pin "AE24") (pinfunction "COMBOPHY_TX1P_AE24") (pintype "passive+no_connect"))
    )
    (net (code "187") (name "unconnected-(U1E-DNC-PadAD20)") (class "Default")
      (node (ref "U1") (pin "AD20") (pinfunction "DNC_AD20") (pintype "passive+no_connect"))
    )
    (net (code "188") (name "unconnected-(U1E-PCIE_CLKINN-PadAE26)") (class "Default")
      (node (ref "U1") (pin "AE26") (pinfunction "PCIE_CLKINN_AE26") (pintype "passive+no_connect"))
    )
    (net (code "189") (name "unconnected-(U1E-PCIE_CLKINP-PadAE25)") (class "Default")
      (node (ref "U1") (pin "AE25") (pinfunction "PCIE_CLKINP_AE25") (pintype "passive+no_connect"))
    )
    (net (code "190") (name "unconnected-(U1E-PCIE_CLKOUTN-PadAG26)") (class "Default")
      (node (ref "U1") (pin "AG26") (pinfunction "PCIE_CLKOUTN_AG26") (pintype "passive+no_connect"))
    )
    (net (code "191") (name "unconnected-(U1E-PCIE_CLKOUTP-PadAF26)") (class "Default")
      (node (ref "U1") (pin "AF26") (pinfunction "PCIE_CLKOUTP_AF26") (pintype "passive+no_connect"))
    )
    (net (code "192") (name "unconnected-(U1E-UCPD1_CC1-PadAB18)") (class "Default")
      (node (ref "U1") (pin "AB18") (pinfunction "UCPD1_CC1_AB18") (pintype "passive+no_connect"))
    )
    (net (code "193") (name "unconnected-(U1E-UCPD1_CC2-PadAA19)") (class "Default")
      (node (ref "U1") (pin "AA19") (pinfunction "UCPD1_CC2_AA19") (pintype "passive+no_connect"))
    )
    (net (code "194") (name "unconnected-(U1E-USB3DR_DM-PadAG22)") (class "Default")
      (node (ref "U1") (pin "AG22") (pinfunction "USB3DR_DM_AG22") (pintype "passive+no_connect"))
    )
    (net (code "195") (name "unconnected-(U1E-USB3DR_DP-PadAF22)") (class "Default")
      (node (ref "U1") (pin "AF22") (pinfunction "USB3DR_DP_AF22") (pintype "passive+no_connect"))
    )
    (net (code "196") (name "unconnected-(U1E-USB3DR_TXRTUNE-PadAF23)") (class "Default")
      (node (ref "U1") (pin "AF23") (pinfunction "USB3DR_TXRTUNE_AF23") (pintype "passive+no_connect"))
    )
    (net (code "197") (name "unconnected-(U1E-USBH_HS_DM-PadAG21)") (class "Default")
      (node (ref "U1") (pin "AG21") (pinfunction "USBH_HS_DM_AG21") (pintype "passive+no_connect"))
    )
    (net (code "198") (name "unconnected-(U1E-USBH_HS_DP-PadAF21)") (class "Default")
      (node (ref "U1") (pin "AF21") (pinfunction "USBH_HS_DP_AF21") (pintype "passive+no_connect"))
    )
    (net (code "199") (name "unconnected-(U1E-USBH_HS_TXRTUNE-PadAE20)") (class "Default")
      (node (ref "U1") (pin "AE20") (pinfunction "USBH_HS_TXRTUNE_AE20") (pintype "passive+no_connect"))
    )
    (net (code "200") (name "unconnected-(U1H-LVDS1_D0N-PadG3)") (class "Default")
      (node (ref "U1") (pin "G3") (pinfunction "LVDS1_D0N_G3") (pintype "passive+no_connect"))
    )
    (net (code "201") (name "unconnected-(U1H-LVDS1_D0P-PadG2)") (class "Default")
      (node (ref "U1") (pin "G2") (pinfunction "LVDS1_D0P_G2") (pintype "passive+no_connect"))
    )
    (net (code "202") (name "unconnected-(U1H-LVDS1_D1N-PadH4)") (class "Default")
      (node (ref "U1") (pin "H4") (pinfunction "LVDS1_D1N_H4") (pintype "passive+no_connect"))
    )
    (net (code "203") (name "unconnected-(U1H-LVDS1_D1P-PadH3)") (class "Default")
      (node (ref "U1") (pin "H3") (pinfunction "LVDS1_D1P_H3") (pintype "passive+no_connect"))
    )
    (net (code "204") (name "unconnected-(U1H-LVDS1_D2N-PadJ2)") (class "Default")
      (node (ref "U1") (pin "J2") (pinfunction "LVDS1_D2N_J2") (pintype "passive+no_connect"))
    )
    (net (code "205") (name "unconnected-(U1H-LVDS1_D2P-PadJ1)") (class "Default")
      (node (ref "U1") (pin "J1") (pinfunction "LVDS1_D2P_J1") (pintype "passive+no_connect"))
    )
    (net (code "206") (name "unconnected-(U1H-LVDS1_D3N-PadL3)") (class "Default")
      (node (ref "U1") (pin "L3") (pinfunction "LVDS1_D3N_L3") (pintype "passive+no_connect"))
    )
    (net (code "207") (name "unconnected-(U1H-LVDS1_D3P-PadL2)") (class "Default")
      (node (ref "U1") (pin "L2") (pinfunction "LVDS1_D3P_L2") (pintype "passive+no_connect"))
    )
    (net (code "208") (name "unconnected-(U1H-LVDS1_D4N-PadK2)") (class "Default")
      (node (ref "U1") (pin "K2") (pinfunction "LVDS1_D4N_K2") (pintype "passive+no_connect"))
    )
    (net (code "209") (name "unconnected-(U1H-LVDS1_D4P-PadK1)") (class "Default")
      (node (ref "U1") (pin "K1") (pinfunction "LVDS1_D4P_K1") (pintype "passive+no_connect"))
    )
    (net (code "210") (name "unconnected-(U1H-LVDS2_D0N-PadB2)") (class "Default")
      (node (ref "U1") (pin "B2") (pinfunction "LVDS2_D0N_B2") (pintype "passive+no_connect"))
    )
    (net (code "211") (name "unconnected-(U1H-LVDS2_D0P-PadB1)") (class "Default")
      (node (ref "U1") (pin "B1") (pinfunction "LVDS2_D0P_B1") (pintype "passive+no_connect"))
    )
    (net (code "212") (name "unconnected-(U1H-LVDS2_D1N-PadC3)") (class "Default")
      (node (ref "U1") (pin "C3") (pinfunction "LVDS2_D1N_C3") (pintype "passive+no_connect"))
    )
    (net (code "213") (name "unconnected-(U1H-LVDS2_D1P-PadC2)") (class "Default")
      (node (ref "U1") (pin "C2") (pinfunction "LVDS2_D1P_C2") (pintype "passive+no_connect"))
    )
    (net (code "214") (name "unconnected-(U1H-LVDS2_D2N-PadD3)") (class "Default")
      (node (ref "U1") (pin "D3") (pinfunction "LVDS2_D2N_D3") (pintype "passive+no_connect"))
    )
    (net (code "215") (name "unconnected-(U1H-LVDS2_D2P-PadE3)") (class "Default")
      (node (ref "U1") (pin "E3") (pinfunction "LVDS2_D2P_E3") (pintype "passive+no_connect"))
    )
    (net (code "216") (name "unconnected-(U1H-LVDS2_D3N-PadE2)") (class "Default")
      (node (ref "U1") (pin "E2") (pinfunction "LVDS2_D3N_E2") (pintype "passive+no_connect"))
    )
    (net (code "217") (name "unconnected-(U1H-LVDS2_D3P-PadE1)") (class "Default")
      (node (ref "U1") (pin "E1") (pinfunction "LVDS2_D3P_E1") (pintype "passive+no_connect"))
    )
    (net (code "218") (name "unconnected-(U1H-LVDS2_D4N-PadF2)") (class "Default")
      (node (ref "U1") (pin "F2") (pinfunction "LVDS2_D4N_F2") (pintype "passive+no_connect"))
    )
    (net (code "219") (name "unconnected-(U1H-LVDS2_D4P-PadF1)") (class "Default")
      (node (ref "U1") (pin "F1") (pinfunction "LVDS2_D4P_F1") (pintype "passive+no_connect"))
    )
    (net (code "220") (name "unconnected-(U1I-CSI_CKN-PadD4)") (class "Default")
      (node (ref "U1") (pin "D4") (pinfunction "CSI_CKN_D4") (pintype "passive+no_connect"))
    )
    (net (code "221") (name "unconnected-(U1I-CSI_CKP-PadC4)") (class "Default")
      (node (ref "U1") (pin "C4") (pinfunction "CSI_CKP_C4") (pintype "passive+no_connect"))
    )
    (net (code "222") (name "unconnected-(U1I-CSI_D0N-PadA3)") (class "Default")
      (node (ref "U1") (pin "A3") (pinfunction "CSI_D0N_A3") (pintype "passive+no_connect"))
    )
    (net (code "223") (name "unconnected-(U1I-CSI_D0P-PadB3)") (class "Default")
      (node (ref "U1") (pin "B3") (pinfunction "CSI_D0P_B3") (pintype "passive+no_connect"))
    )
    (net (code "224") (name "unconnected-(U1I-CSI_D1N-PadC5)") (class "Default")
      (node (ref "U1") (pin "C5") (pinfunction "CSI_D1N_C5") (pintype "passive+no_connect"))
    )
    (net (code "225") (name "unconnected-(U1I-CSI_D1P-PadB5)") (class "Default")
      (node (ref "U1") (pin "B5") (pinfunction "CSI_D1P_B5") (pintype "passive+no_connect"))
    )
    (net (code "226") (name "unconnected-(U1I-CSI_REXT-PadF6)") (class "Default")
      (node (ref "U1") (pin "F6") (pinfunction "CSI_REXT_F6") (pintype "passive+no_connect"))
    )
  )
)
